# SmartSwitch.net
KiCad netlist of a schematic drawn in Altium Designer
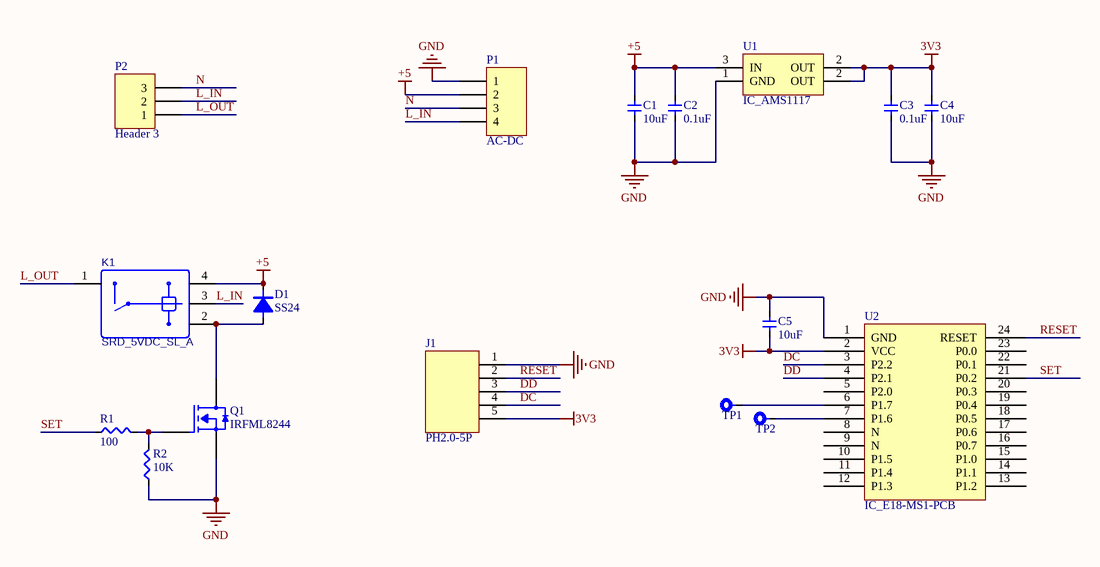
[diagram p0: SmartSwitch.SchDoc]

(export (version "E")
  (design (tool "Eeschema 10.0.6"))
  (components
    (comp (ref "C1")
      (value "10uF")
      (footprint "C 0603_M")
      (description "电容")
      (libsource (lib "01 Base") (part "CAP"))
    )
    (comp (ref "C2")
      (value "0.1uF")
      (footprint "C 0603_M")
      (description "电容")
      (libsource (lib "01 Base") (part "CAP"))
    )
    (comp (ref "C3")
      (value "0.1uF")
      (footprint "C 0603_M")
      (description "电容")
      (libsource (lib "01 Base") (part "CAP"))
    )
    (comp (ref "C4")
      (value "10uF")
      (footprint "C 0603_M")
      (description "电容")
      (libsource (lib "01 Base") (part "CAP"))
    )
    (comp (ref "C5")
      (value "10uF")
      (footprint "C 0603_M")
      (description "电容")
      (libsource (lib "01 Base") (part "CAP"))
    )
    (comp (ref "D1")
      (value "SS24")
      (footprint "D SMA/DO-214AC")
      (description "普通二极管")
      (libsource (lib "01 Base") (part "DIODE"))
    )
    (comp (ref "J1") (value "PH2.0-5P") (footprint "PH2.0-LI-5P") (libsource (lib "04 PH") (part "PH2.0-5P")))
    (comp (ref "K1")
      (value "SRD_5VDC_SL_A")
      (footprint "K_SRD_XXVDC-XX-A")
      (description "一组常开")
      (fields
        (field (name "BOM_SUPPLIER PART") "C140615")
        (field (name "BOM_MANUFACTURER PART") "SRD-5VDC-SL-A")
        (field (name "CONTRIBUTOR") "LCSC")
      )
      (libsource (lib "08 KEY") (part "K_SRD_5VDC_SL_A"))
    )
    (comp (ref "P1")
      (value "AC-DC")
      (footprint "AC_DC")
      (description "Header, 4-Pin")
      (fields (field (name "PUBLISHER") "Altium Limited"))
      (libsource (lib "Miscellaneous Connectors") (part "Header 4"))
    )
    (comp (ref "P2")
      (value "Header 3")
      (footprint "P5.08_3P")
      (description "Header, 3-Pin")
      (fields (field (name "PUBLISHER") "Altium Limited"))
      (libsource (lib "Miscellaneous Connectors") (part "Header 3"))
    )
    (comp (ref "Q1")
      (value "IRFML8244")
      (footprint "SOT23-3M")
      (description "NMOS")
      (libsource (lib "MySCHLIB") (part "TX_MOS-N"))
    )
    (comp (ref "R1")
      (value "100")
      (footprint "R 0603_M")
      (description "电阻")
      (libsource (lib "01 Base") (part "RES"))
    )
    (comp (ref "R2")
      (value "10K")
      (footprint "R 0603_M")
      (description "电阻")
      (libsource (lib "01 Base") (part "RES"))
    )
    (comp (ref "TP1")
      (value "TP")
      (footprint "TP_BIG")
      (description "测试点或焊盘")
      (libsource (lib "01 Base") (part "TP"))
    )
    (comp (ref "TP2")
      (value "TP")
      (footprint "TP_BIG")
      (description "测试点或焊盘")
      (libsource (lib "01 Base") (part "TP"))
    )
    (comp (ref "U1")
      (value "IC_AMS1117")
      (footprint "SOT89")
      (description "线性稳压器")
      (libsource (lib "06 IC") (part "U_LDO_AMS1117"))
    )
    (comp (ref "U2")
      (value "IC_E18-MS1-PCB")
      (footprint "E18_MS1_PCB")
      (description "Zigbee模块")
      (libsource (lib "MySCHLIB") (part "IC_E18-MS1-PCB"))
    )
  )
  (nets
    (net (code "1") (name "+5") (class "Default")
      (node (ref "C1") (pin "1") (pinfunction "1_1") (pintype "passive"))
      (node (ref "C2") (pin "1") (pinfunction "1_1") (pintype "passive"))
      (node (ref "D1") (pin "K") (pinfunction "K_K") (pintype "passive"))
      (node (ref "K1") (pin "4") (pinfunction "4_4") (pintype "passive"))
      (node (ref "P1") (pin "2") (pinfunction "2_2") (pintype "passive"))
      (node (ref "U1") (pin "3") (pinfunction "IN_3") (pintype "passive"))
    )
    (net (code "2") (name "/DC") (class "Default")
      (node (ref "J1") (pin "4") (pinfunction "4_4") (pintype "passive"))
      (node (ref "U2") (pin "3") (pinfunction "P2.2_3") (pintype "passive"))
    )
    (net (code "3") (name "/DD") (class "Default")
      (node (ref "J1") (pin "3") (pinfunction "3_3") (pintype "passive"))
      (node (ref "U2") (pin "4") (pinfunction "P2.1_4") (pintype "passive"))
    )
    (net (code "4") (name "/L_IN") (class "Default")
      (node (ref "K1") (pin "3") (pinfunction "3_3") (pintype "passive"))
      (node (ref "P1") (pin "4") (pinfunction "4_4") (pintype "passive"))
      (node (ref "P2") (pin "2") (pinfunction "2_2") (pintype "passive"))
    )
    (net (code "5") (name "/L_OUT") (class "Default")
      (node (ref "K1") (pin "1") (pinfunction "1_1") (pintype "passive"))
      (node (ref "P2") (pin "1") (pinfunction "1_1") (pintype "passive"))
    )
    (net (code "6") (name "/N") (class "Default")
      (node (ref "P1") (pin "3") (pinfunction "3_3") (pintype "passive"))
      (node (ref "P2") (pin "3") (pinfunction "3_3") (pintype "passive"))
    )
    (net (code "7") (name "/RESET") (class "Default")
      (node (ref "J1") (pin "2") (pinfunction "2_2") (pintype "passive"))
      (node (ref "U2") (pin "24") (pinfunction "RESET_24") (pintype "passive"))
    )
    (net (code "8") (name "/SET") (class "Default")
      (node (ref "R1") (pin "1") (pinfunction "1_1") (pintype "passive"))
      (node (ref "U2") (pin "21") (pinfunction "P0.2_21") (pintype "passive"))
    )
    (net (code "9") (name "3V3") (class "Default")
      (node (ref "C3") (pin "1") (pinfunction "1_1") (pintype "passive"))
      (node (ref "C4") (pin "1") (pinfunction "1_1") (pintype "passive"))
      (node (ref "C5") (pin "2") (pinfunction "2_2") (pintype "passive"))
      (node (ref "J1") (pin "5") (pinfunction "5_5") (pintype "passive"))
      (node (ref "U1") (pin "2") (pinfunction "OUT_2") (pintype "passive"))
      (node (ref "U2") (pin "2") (pinfunction "VCC_2") (pintype "passive"))
    )
    (net (code "10") (name "GND") (class "Default")
      (node (ref "C1") (pin "2") (pinfunction "2_2") (pintype "passive"))
      (node (ref "C2") (pin "2") (pinfunction "2_2") (pintype "passive"))
      (node (ref "C3") (pin "2") (pinfunction "2_2") (pintype "passive"))
      (node (ref "C4") (pin "2") (pinfunction "2_2") (pintype "passive"))
      (node (ref "C5") (pin "1") (pinfunction "1_1") (pintype "passive"))
      (node (ref "J1") (pin "1") (pinfunction "1_1") (pintype "passive"))
      (node (ref "P1") (pin "1") (pinfunction "1_1") (pintype "passive"))
      (node (ref "Q1") (pin "2") (pinfunction "S_2") (pintype "passive"))
      (node (ref "R2") (pin "1") (pinfunction "1_1") (pintype "passive"))
      (node (ref "U1") (pin "1") (pinfunction "GND_1") (pintype "passive"))
      (node (ref "U2") (pin "1") (pinfunction "GND_1") (pintype "passive"))
    )
    (net (code "11") (name "Net-(Q1-D)") (class "Default")
      (node (ref "D1") (pin "A") (pinfunction "A_A") (pintype "passive"))
      (node (ref "K1") (pin "2") (pinfunction "2_2") (pintype "passive"))
      (node (ref "Q1") (pin "3") (pinfunction "D_3") (pintype "passive"))
    )
    (net (code "12") (name "Net-(Q1-G)") (class "Default")
      (node (ref "Q1") (pin "1") (pinfunction "G_1") (pintype "passive"))
      (node (ref "R1") (pin "2") (pinfunction "2_2") (pintype "passive"))
      (node (ref "R2") (pin "2") (pinfunction "2_2") (pintype "passive"))
    )
    (net (code "13") (name "Net-(U2-P1.6)") (class "Default")
      (node (ref "TP2") (pin "1") (pinfunction "1_1") (pintype "passive"))
      (node (ref "U2") (pin "7") (pinfunction "P1.6_7") (pintype "passive"))
    )
    (net (code "14") (name "Net-(U2-P1.7)") (class "Default")
      (node (ref "TP1") (pin "1") (pinfunction "1_1") (pintype "passive"))
      (node (ref "U2") (pin "6") (pinfunction "P1.7_6") (pintype "passive"))
    )
    (net (code "15") (name "unconnected-(U2-N-Pad8)") (class "Default")
      (node (ref "U2") (pin "8") (pinfunction "N_8") (pintype "passive"))
    )
    (net (code "16") (name "unconnected-(U2-N-Pad9)") (class "Default")
      (node (ref "U2") (pin "9") (pinfunction "N_9") (pintype "passive"))
    )
    (net (code "17") (name "unconnected-(U2-P0.0-Pad23)") (class "Default")
      (node (ref "U2") (pin "23") (pinfunction "P0.0_23") (pintype "passive"))
    )
    (net (code "18") (name "unconnected-(U2-P0.1-Pad22)") (class "Default")
      (node (ref "U2") (pin "22") (pinfunction "P0.1_22") (pintype "passive"))
    )
    (net (code "19") (name "unconnected-(U2-P0.3-Pad20)") (class "Default")
      (node (ref "U2") (pin "20") (pinfunction "P0.3_20") (pintype "passive"))
    )
    (net (code "20") (name "unconnected-(U2-P0.4-Pad19)") (class "Default")
      (node (ref "U2") (pin "19") (pinfunction "P0.4_19") (pintype "passive"))
    )
    (net (code "21") (name "unconnected-(U2-P0.5-Pad18)") (class "Default")
      (node (ref "U2") (pin "18") (pinfunction "P0.5_18") (pintype "passive"))
    )
    (net (code "22") (name "unconnected-(U2-P0.6-Pad17)") (class "Default")
      (node (ref "U2") (pin "17") (pinfunction "P0.6_17") (pintype "passive"))
    )
    (net (code "23") (name "unconnected-(U2-P0.7-Pad16)") (class "Default")
      (node (ref "U2") (pin "16") (pinfunction "P0.7_16") (pintype "passive"))
    )
    (net (code "24") (name "unconnected-(U2-P1.0-Pad15)") (class "Default")
      (node (ref "U2") (pin "15") (pinfunction "P1.0_15") (pintype "passive"))
    )
    (net (code "25") (name "unconnected-(U2-P1.1-Pad14)") (class "Default")
      (node (ref "U2") (pin "14") (pinfunction "P1.1_14") (pintype "passive"))
    )
    (net (code "26") (name "unconnected-(U2-P1.2-Pad13)") (class "Default")
      (node (ref "U2") (pin "13") (pinfunction "P1.2_13") (pintype "passive"))
    )
    (net (code "27") (name "unconnected-(U2-P1.3-Pad12)") (class "Default")
      (node (ref "U2") (pin "12") (pinfunction "P1.3_12") (pintype "passive"))
    )
    (net (code "28") (name "unconnected-(U2-P1.4-Pad11)") (class "Default")
      (node (ref "U2") (pin "11") (pinfunction "P1.4_11") (pintype "passive"))
    )
    (net (code "29") (name "unconnected-(U2-P1.5-Pad10)") (class "Default")
      (node (ref "U2") (pin "10") (pinfunction "P1.5_10") (pintype "passive"))
    )
    (net (code "30") (name "unconnected-(U2-P2.0-Pad5)") (class "Default")
      (node (ref "U2") (pin "5") (pinfunction "P2.0_5") (pintype "passive"))
    )
  )
)
